# FPGA_Banks.net
KiCad netlist of a schematic drawn in Altium Designer
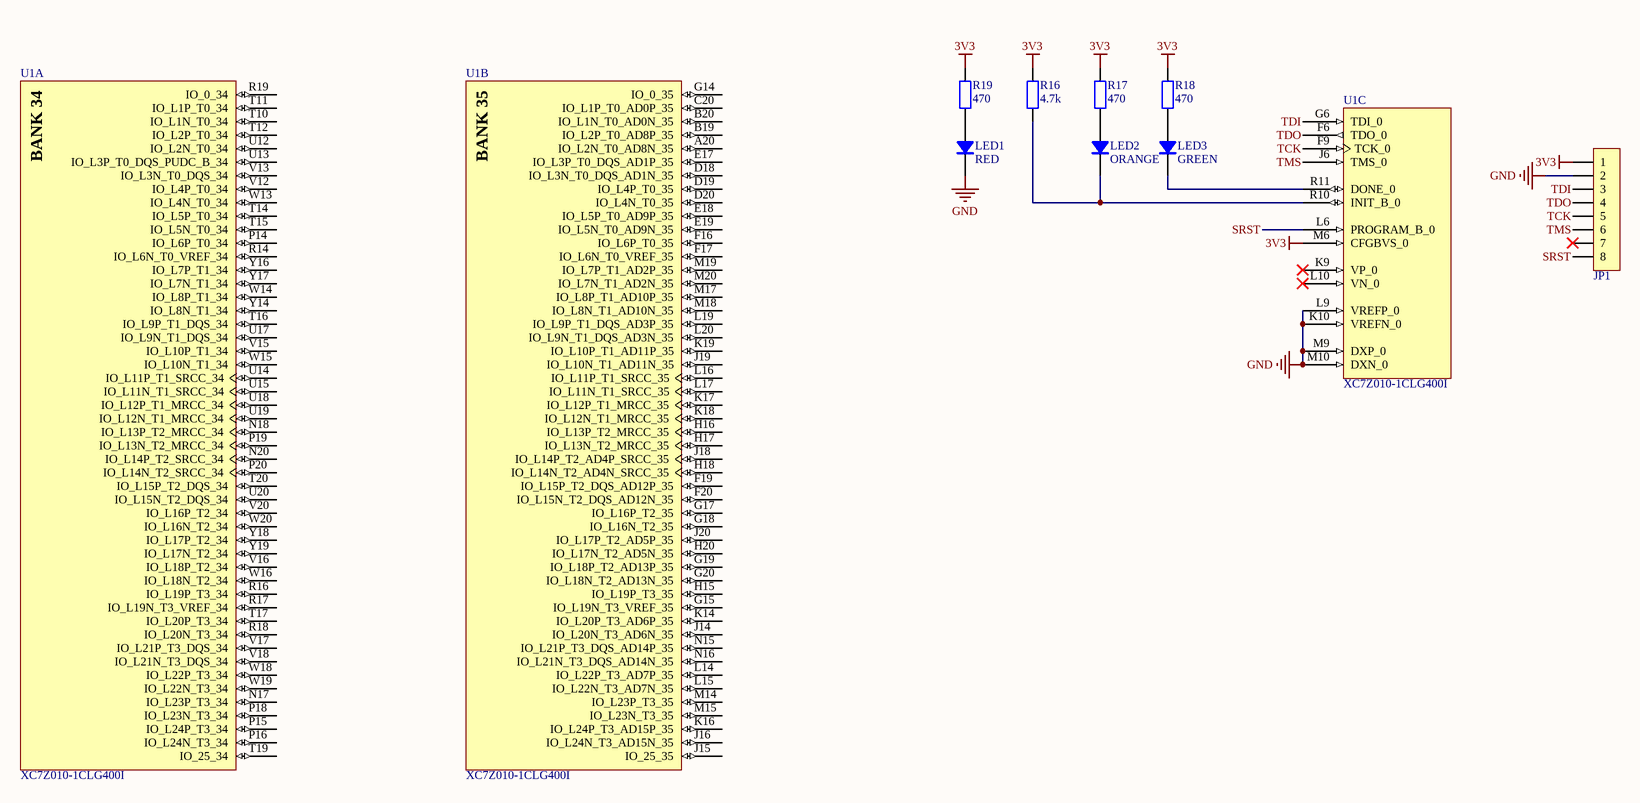
[diagram p0: FPGA_Banks.SchDoc]

(export (version "E")
  (design (tool "Eeschema 10.0.6"))
  (components
    (comp (ref "JP1")
      (value "HDR-1X8")
      (footprint "HDR2.54-LI-8P")
      (description "8P接插件")
      (fields (field (name "版权归属") "源创客"))
      (libsource (lib "Pin2.54") (part "Header 8"))
    )
    (comp (ref "LED1") (value "RED") (footprint "LED 0603R") (libsource (lib "Passive") (part "D")))
    (comp (ref "LED2") (value "ORANGE") (footprint "LED 0603Y") (libsource (lib "Passive") (part "D")))
    (comp (ref "LED3") (value "GREEN") (footprint "LED 0603G") (libsource (lib "Passive") (part "D")))
    (comp (ref "R16") (value "4.7k") (footprint "R0402") (libsource (lib "Passive") (part "R")))
    (comp (ref "R17") (value "470") (footprint "R0402") (libsource (lib "Passive") (part "R")))
    (comp (ref "R18") (value "470") (footprint "R0402") (libsource (lib "Passive") (part "R")))
    (comp (ref "R19") (value "470") (footprint "R0402") (libsource (lib "Passive") (part "R")))
    (comp (ref "U1")
      (value "XC7Z010-1CLG400I")
      (footprint "CLG400")
      (fields (field (name "GENERIC PART NUMBER") "XC7Z010"))
      (libsource (lib "Altium Content Vault") (part "XNLX-XC7Z010-CLG400"))
    )
  )
  (nets
    (net (code "1") (name "/SRST") (class "Default")
      (node (ref "JP1") (pin "8") (pinfunction "8_8") (pintype "passive"))
      (node (ref "U1") (pin "L6") (pinfunction "PROGRAM_B_0_L6") (pintype "input"))
    )
    (net (code "2") (name "/TCK") (class "Default")
      (node (ref "JP1") (pin "5") (pinfunction "5_5") (pintype "passive"))
      (node (ref "U1") (pin "F9") (pinfunction "TCK_0_F9") (pintype "input"))
    )
    (net (code "3") (name "/TDI") (class "Default")
      (node (ref "JP1") (pin "3") (pinfunction "3_3") (pintype "passive"))
      (node (ref "U1") (pin "G6") (pinfunction "TDI_0_G6") (pintype "input"))
    )
    (net (code "4") (name "/TDO") (class "Default")
      (node (ref "JP1") (pin "4") (pinfunction "4_4") (pintype "passive"))
      (node (ref "U1") (pin "F6") (pinfunction "TDO_0_F6") (pintype "output"))
    )
    (net (code "5") (name "/TMS") (class "Default")
      (node (ref "JP1") (pin "6") (pinfunction "6_6") (pintype "passive"))
      (node (ref "U1") (pin "J6") (pinfunction "TMS_0_J6") (pintype "input"))
    )
    (net (code "6") (name "3V3") (class "Default")
      (node (ref "JP1") (pin "1") (pinfunction "1_1") (pintype "passive"))
      (node (ref "R16") (pin "1") (pinfunction "1_1") (pintype "passive"))
      (node (ref "R17") (pin "1") (pinfunction "1_1") (pintype "passive"))
      (node (ref "R18") (pin "1") (pinfunction "1_1") (pintype "passive"))
      (node (ref "R19") (pin "1") (pinfunction "1_1") (pintype "passive"))
      (node (ref "U1") (pin "M6") (pinfunction "CFGBVS_0_M6") (pintype "input"))
    )
    (net (code "7") (name "GND") (class "Default")
      (node (ref "JP1") (pin "2") (pinfunction "2_2") (pintype "passive"))
      (node (ref "LED1") (pin "2") (pinfunction "K_2") (pintype "passive"))
      (node (ref "U1") (pin "K10") (pinfunction "VREFN_0_K10") (pintype "input"))
      (node (ref "U1") (pin "L9") (pinfunction "VREFP_0_L9") (pintype "input"))
      (node (ref "U1") (pin "M10") (pinfunction "DXN_0_M10") (pintype "input"))
      (node (ref "U1") (pin "M9") (pinfunction "DXP_0_M9") (pintype "input"))
    )
    (net (code "8") (name "Net-(LED1-A)") (class "Default")
      (node (ref "LED1") (pin "1") (pinfunction "A_1") (pintype "passive"))
      (node (ref "R19") (pin "2") (pinfunction "2_2") (pintype "passive"))
    )
    (net (code "9") (name "Net-(LED2-A)") (class "Default")
      (node (ref "LED2") (pin "1") (pinfunction "A_1") (pintype "passive"))
      (node (ref "R17") (pin "2") (pinfunction "2_2") (pintype "passive"))
    )
    (net (code "10") (name "Net-(LED2-K)") (class "Default")
      (node (ref "LED2") (pin "2") (pinfunction "K_2") (pintype "passive"))
      (node (ref "R16") (pin "2") (pinfunction "2_2") (pintype "passive"))
      (node (ref "U1") (pin "R10") (pinfunction "INIT_B_0_R10") (pintype "bidirectional"))
    )
    (net (code "11") (name "Net-(LED3-A)") (class "Default")
      (node (ref "LED3") (pin "1") (pinfunction "A_1") (pintype "passive"))
      (node (ref "R18") (pin "2") (pinfunction "2_2") (pintype "passive"))
    )
    (net (code "12") (name "Net-(LED3-K)") (class "Default")
      (node (ref "LED3") (pin "2") (pinfunction "K_2") (pintype "passive"))
      (node (ref "U1") (pin "R11") (pinfunction "DONE_0_R11") (pintype "bidirectional"))
    )
    (net (code "13") (name "unconnected-(JP1-Pad7)") (class "Default")
      (node (ref "JP1") (pin "7") (pinfunction "7_7") (pintype "passive+no_connect"))
    )
    (net (code "14") (name "unconnected-(U1A-IO_0_34-PadR19)") (class "Default")
      (node (ref "U1") (pin "R19") (pinfunction "IO_0_34_R19") (pintype "bidirectional"))
    )
    (net (code "15") (name "unconnected-(U1A-IO_25_34-PadT19)") (class "Default")
      (node (ref "U1") (pin "T19") (pinfunction "IO_25_34_T19") (pintype "bidirectional"))
    )
    (net (code "16") (name "unconnected-(U1A-IO_L1N_T0_34-PadT10)") (class "Default")
      (node (ref "U1") (pin "T10") (pinfunction "IO_L1N_T0_34_T10") (pintype "bidirectional"))
    )
    (net (code "17") (name "unconnected-(U1A-IO_L1P_T0_34-PadT11)") (class "Default")
      (node (ref "U1") (pin "T11") (pinfunction "IO_L1P_T0_34_T11") (pintype "bidirectional"))
    )
    (net (code "18") (name "unconnected-(U1A-IO_L2N_T0_34-PadU12)") (class "Default")
      (node (ref "U1") (pin "U12") (pinfunction "IO_L2N_T0_34_U12") (pintype "bidirectional"))
    )
    (net (code "19") (name "unconnected-(U1A-IO_L2P_T0_34-PadT12)") (class "Default")
      (node (ref "U1") (pin "T12") (pinfunction "IO_L2P_T0_34_T12") (pintype "bidirectional"))
    )
    (net (code "20") (name "unconnected-(U1A-IO_L3N_T0_DQS_34-PadV13)") (class "Default")
      (node (ref "U1") (pin "V13") (pinfunction "IO_L3N_T0_DQS_34_V13") (pintype "bidirectional"))
    )
    (net (code "21") (name "unconnected-(U1A-IO_L3P_T0_DQS_PUDC_B_34-PadU13)") (class "Default")
      (node (ref "U1") (pin "U13") (pinfunction "IO_L3P_T0_DQS_PUDC_B_34_U13") (pintype "bidirectional"))
    )
    (net (code "22") (name "unconnected-(U1A-IO_L4N_T0_34-PadW13)") (class "Default")
      (node (ref "U1") (pin "W13") (pinfunction "IO_L4N_T0_34_W13") (pintype "bidirectional"))
    )
    (net (code "23") (name "unconnected-(U1A-IO_L4P_T0_34-PadV12)") (class "Default")
      (node (ref "U1") (pin "V12") (pinfunction "IO_L4P_T0_34_V12") (pintype "bidirectional"))
    )
    (net (code "24") (name "unconnected-(U1A-IO_L5N_T0_34-PadT15)") (class "Default")
      (node (ref "U1") (pin "T15") (pinfunction "IO_L5N_T0_34_T15") (pintype "bidirectional"))
    )
    (net (code "25") (name "unconnected-(U1A-IO_L5P_T0_34-PadT14)") (class "Default")
      (node (ref "U1") (pin "T14") (pinfunction "IO_L5P_T0_34_T14") (pintype "bidirectional"))
    )
    (net (code "26") (name "unconnected-(U1A-IO_L6N_T0_VREF_34-PadR14)") (class "Default")
      (node (ref "U1") (pin "R14") (pinfunction "IO_L6N_T0_VREF_34_R14") (pintype "bidirectional"))
    )
    (net (code "27") (name "unconnected-(U1A-IO_L6P_T0_34-PadP14)") (class "Default")
      (node (ref "U1") (pin "P14") (pinfunction "IO_L6P_T0_34_P14") (pintype "bidirectional"))
    )
    (net (code "28") (name "unconnected-(U1A-IO_L7N_T1_34-PadY17)") (class "Default")
      (node (ref "U1") (pin "Y17") (pinfunction "IO_L7N_T1_34_Y17") (pintype "bidirectional"))
    )
    (net (code "29") (name "unconnected-(U1A-IO_L7P_T1_34-PadY16)") (class "Default")
      (node (ref "U1") (pin "Y16") (pinfunction "IO_L7P_T1_34_Y16") (pintype "bidirectional"))
    )
    (net (code "30") (name "unconnected-(U1A-IO_L8N_T1_34-PadY14)") (class "Default")
      (node (ref "U1") (pin "Y14") (pinfunction "IO_L8N_T1_34_Y14") (pintype "bidirectional"))
    )
    (net (code "31") (name "unconnected-(U1A-IO_L8P_T1_34-PadW14)") (class "Default")
      (node (ref "U1") (pin "W14") (pinfunction "IO_L8P_T1_34_W14") (pintype "bidirectional"))
    )
    (net (code "32") (name "unconnected-(U1A-IO_L9N_T1_DQS_34-PadU17)") (class "Default")
      (node (ref "U1") (pin "U17") (pinfunction "IO_L9N_T1_DQS_34_U17") (pintype "bidirectional"))
    )
    (net (code "33") (name "unconnected-(U1A-IO_L9P_T1_DQS_34-PadT16)") (class "Default")
      (node (ref "U1") (pin "T16") (pinfunction "IO_L9P_T1_DQS_34_T16") (pintype "bidirectional"))
    )
    (net (code "34") (name "unconnected-(U1A-IO_L10N_T1_34-PadW15)") (class "Default")
      (node (ref "U1") (pin "W15") (pinfunction "IO_L10N_T1_34_W15") (pintype "bidirectional"))
    )
    (net (code "35") (name "unconnected-(U1A-IO_L10P_T1_34-PadV15)") (class "Default")
      (node (ref "U1") (pin "V15") (pinfunction "IO_L10P_T1_34_V15") (pintype "bidirectional"))
    )
    (net (code "36") (name "unconnected-(U1A-IO_L11N_T1_SRCC_34-PadU15)") (class "Default")
      (node (ref "U1") (pin "U15") (pinfunction "IO_L11N_T1_SRCC_34_U15") (pintype "bidirectional"))
    )
    (net (code "37") (name "unconnected-(U1A-IO_L11P_T1_SRCC_34-PadU14)") (class "Default")
      (node (ref "U1") (pin "U14") (pinfunction "IO_L11P_T1_SRCC_34_U14") (pintype "bidirectional"))
    )
    (net (code "38") (name "unconnected-(U1A-IO_L12N_T1_MRCC_34-PadU19)") (class "Default")
      (node (ref "U1") (pin "U19") (pinfunction "IO_L12N_T1_MRCC_34_U19") (pintype "bidirectional"))
    )
    (net (code "39") (name "unconnected-(U1A-IO_L12P_T1_MRCC_34-PadU18)") (class "Default")
      (node (ref "U1") (pin "U18") (pinfunction "IO_L12P_T1_MRCC_34_U18") (pintype "bidirectional"))
    )
    (net (code "40") (name "unconnected-(U1A-IO_L13N_T2_MRCC_34-PadP19)") (class "Default")
      (node (ref "U1") (pin "P19") (pinfunction "IO_L13N_T2_MRCC_34_P19") (pintype "bidirectional"))
    )
    (net (code "41") (name "unconnected-(U1A-IO_L13P_T2_MRCC_34-PadN18)") (class "Default")
      (node (ref "U1") (pin "N18") (pinfunction "IO_L13P_T2_MRCC_34_N18") (pintype "bidirectional"))
    )
    (net (code "42") (name "unconnected-(U1A-IO_L14N_T2_SRCC_34-PadP20)") (class "Default")
      (node (ref "U1") (pin "P20") (pinfunction "IO_L14N_T2_SRCC_34_P20") (pintype "bidirectional"))
    )
    (net (code "43") (name "unconnected-(U1A-IO_L14P_T2_SRCC_34-PadN20)") (class "Default")
      (node (ref "U1") (pin "N20") (pinfunction "IO_L14P_T2_SRCC_34_N20") (pintype "bidirectional"))
    )
    (net (code "44") (name "unconnected-(U1A-IO_L15N_T2_DQS_34-PadU20)") (class "Default")
      (node (ref "U1") (pin "U20") (pinfunction "IO_L15N_T2_DQS_34_U20") (pintype "bidirectional"))
    )
    (net (code "45") (name "unconnected-(U1A-IO_L15P_T2_DQS_34-PadT20)") (class "Default")
      (node (ref "U1") (pin "T20") (pinfunction "IO_L15P_T2_DQS_34_T20") (pintype "bidirectional"))
    )
    (net (code "46") (name "unconnected-(U1A-IO_L16N_T2_34-PadW20)") (class "Default")
      (node (ref "U1") (pin "W20") (pinfunction "IO_L16N_T2_34_W20") (pintype "bidirectional"))
    )
    (net (code "47") (name "unconnected-(U1A-IO_L16P_T2_34-PadV20)") (class "Default")
      (node (ref "U1") (pin "V20") (pinfunction "IO_L16P_T2_34_V20") (pintype "bidirectional"))
    )
    (net (code "48") (name "unconnected-(U1A-IO_L17N_T2_34-PadY19)") (class "Default")
      (node (ref "U1") (pin "Y19") (pinfunction "IO_L17N_T2_34_Y19") (pintype "bidirectional"))
    )
    (net (code "49") (name "unconnected-(U1A-IO_L17P_T2_34-PadY18)") (class "Default")
      (node (ref "U1") (pin "Y18") (pinfunction "IO_L17P_T2_34_Y18") (pintype "bidirectional"))
    )
    (net (code "50") (name "unconnected-(U1A-IO_L18N_T2_34-PadW16)") (class "Default")
      (node (ref "U1") (pin "W16") (pinfunction "IO_L18N_T2_34_W16") (pintype "bidirectional"))
    )
    (net (code "51") (name "unconnected-(U1A-IO_L18P_T2_34-PadV16)") (class "Default")
      (node (ref "U1") (pin "V16") (pinfunction "IO_L18P_T2_34_V16") (pintype "bidirectional"))
    )
    (net (code "52") (name "unconnected-(U1A-IO_L19N_T3_VREF_34-PadR17)") (class "Default")
      (node (ref "U1") (pin "R17") (pinfunction "IO_L19N_T3_VREF_34_R17") (pintype "bidirectional"))
    )
    (net (code "53") (name "unconnected-(U1A-IO_L19P_T3_34-PadR16)") (class "Default")
      (node (ref "U1") (pin "R16") (pinfunction "IO_L19P_T3_34_R16") (pintype "bidirectional"))
    )
    (net (code "54") (name "unconnected-(U1A-IO_L20N_T3_34-PadR18)") (class "Default")
      (node (ref "U1") (pin "R18") (pinfunction "IO_L20N_T3_34_R18") (pintype "bidirectional"))
    )
    (net (code "55") (name "unconnected-(U1A-IO_L20P_T3_34-PadT17)") (class "Default")
      (node (ref "U1") (pin "T17") (pinfunction "IO_L20P_T3_34_T17") (pintype "bidirectional"))
    )
    (net (code "56") (name "unconnected-(U1A-IO_L21N_T3_DQS_34-PadV18)") (class "Default")
      (node (ref "U1") (pin "V18") (pinfunction "IO_L21N_T3_DQS_34_V18") (pintype "bidirectional"))
    )
    (net (code "57") (name "unconnected-(U1A-IO_L21P_T3_DQS_34-PadV17)") (class "Default")
      (node (ref "U1") (pin "V17") (pinfunction "IO_L21P_T3_DQS_34_V17") (pintype "bidirectional"))
    )
    (net (code "58") (name "unconnected-(U1A-IO_L22N_T3_34-PadW19)") (class "Default")
      (node (ref "U1") (pin "W19") (pinfunction "IO_L22N_T3_34_W19") (pintype "bidirectional"))
    )
    (net (code "59") (name "unconnected-(U1A-IO_L22P_T3_34-PadW18)") (class "Default")
      (node (ref "U1") (pin "W18") (pinfunction "IO_L22P_T3_34_W18") (pintype "bidirectional"))
    )
    (net (code "60") (name "unconnected-(U1A-IO_L23N_T3_34-PadP18)") (class "Default")
      (node (ref "U1") (pin "P18") (pinfunction "IO_L23N_T3_34_P18") (pintype "bidirectional"))
    )
    (net (code "61") (name "unconnected-(U1A-IO_L23P_T3_34-PadN17)") (class "Default")
      (node (ref "U1") (pin "N17") (pinfunction "IO_L23P_T3_34_N17") (pintype "bidirectional"))
    )
    (net (code "62") (name "unconnected-(U1A-IO_L24N_T3_34-PadP16)") (class "Default")
      (node (ref "U1") (pin "P16") (pinfunction "IO_L24N_T3_34_P16") (pintype "bidirectional"))
    )
    (net (code "63") (name "unconnected-(U1A-IO_L24P_T3_34-PadP15)") (class "Default")
      (node (ref "U1") (pin "P15") (pinfunction "IO_L24P_T3_34_P15") (pintype "bidirectional"))
    )
    (net (code "64") (name "unconnected-(U1B-IO_0_35-PadG14)") (class "Default")
      (node (ref "U1") (pin "G14") (pinfunction "IO_0_35_G14") (pintype "bidirectional"))
    )
    (net (code "65") (name "unconnected-(U1B-IO_25_35-PadJ15)") (class "Default")
      (node (ref "U1") (pin "J15") (pinfunction "IO_25_35_J15") (pintype "bidirectional"))
    )
    (net (code "66") (name "unconnected-(U1B-IO_L1N_T0_AD0N_35-PadB20)") (class "Default")
      (node (ref "U1") (pin "B20") (pinfunction "IO_L1N_T0_AD0N_35_B20") (pintype "bidirectional"))
    )
    (net (code "67") (name "unconnected-(U1B-IO_L1P_T0_AD0P_35-PadC20)") (class "Default")
      (node (ref "U1") (pin "C20") (pinfunction "IO_L1P_T0_AD0P_35_C20") (pintype "bidirectional"))
    )
    (net (code "68") (name "unconnected-(U1B-IO_L2N_T0_AD8N_35-PadA20)") (class "Default")
      (node (ref "U1") (pin "A20") (pinfunction "IO_L2N_T0_AD8N_35_A20") (pintype "bidirectional"))
    )
    (net (code "69") (name "unconnected-(U1B-IO_L2P_T0_AD8P_35-PadB19)") (class "Default")
      (node (ref "U1") (pin "B19") (pinfunction "IO_L2P_T0_AD8P_35_B19") (pintype "bidirectional"))
    )
    (net (code "70") (name "unconnected-(U1B-IO_L3N_T0_DQS_AD1N_35-PadD18)") (class "Default")
      (node (ref "U1") (pin "D18") (pinfunction "IO_L3N_T0_DQS_AD1N_35_D18") (pintype "bidirectional"))
    )
    (net (code "71") (name "unconnected-(U1B-IO_L3P_T0_DQS_AD1P_35-PadE17)") (class "Default")
      (node (ref "U1") (pin "E17") (pinfunction "IO_L3P_T0_DQS_AD1P_35_E17") (pintype "bidirectional"))
    )
    (net (code "72") (name "unconnected-(U1B-IO_L4N_T0_35-PadD20)") (class "Default")
      (node (ref "U1") (pin "D20") (pinfunction "IO_L4N_T0_35_D20") (pintype "bidirectional"))
    )
    (net (code "73") (name "unconnected-(U1B-IO_L4P_T0_35-PadD19)") (class "Default")
      (node (ref "U1") (pin "D19") (pinfunction "IO_L4P_T0_35_D19") (pintype "bidirectional"))
    )
    (net (code "74") (name "unconnected-(U1B-IO_L5N_T0_AD9N_35-PadE19)") (class "Default")
      (node (ref "U1") (pin "E19") (pinfunction "IO_L5N_T0_AD9N_35_E19") (pintype "bidirectional"))
    )
    (net (code "75") (name "unconnected-(U1B-IO_L5P_T0_AD9P_35-PadE18)") (class "Default")
      (node (ref "U1") (pin "E18") (pinfunction "IO_L5P_T0_AD9P_35_E18") (pintype "bidirectional"))
    )
    (net (code "76") (name "unconnected-(U1B-IO_L6N_T0_VREF_35-PadF17)") (class "Default")
      (node (ref "U1") (pin "F17") (pinfunction "IO_L6N_T0_VREF_35_F17") (pintype "bidirectional"))
    )
    (net (code "77") (name "unconnected-(U1B-IO_L6P_T0_35-PadF16)") (class "Default")
      (node (ref "U1") (pin "F16") (pinfunction "IO_L6P_T0_35_F16") (pintype "bidirectional"))
    )
    (net (code "78") (name "unconnected-(U1B-IO_L7N_T1_AD2N_35-PadM20)") (class "Default")
      (node (ref "U1") (pin "M20") (pinfunction "IO_L7N_T1_AD2N_35_M20") (pintype "bidirectional"))
    )
    (net (code "79") (name "unconnected-(U1B-IO_L7P_T1_AD2P_35-PadM19)") (class "Default")
      (node (ref "U1") (pin "M19") (pinfunction "IO_L7P_T1_AD2P_35_M19") (pintype "bidirectional"))
    )
    (net (code "80") (name "unconnected-(U1B-IO_L8N_T1_AD10N_35-PadM18)") (class "Default")
      (node (ref "U1") (pin "M18") (pinfunction "IO_L8N_T1_AD10N_35_M18") (pintype "bidirectional"))
    )
    (net (code "81") (name "unconnected-(U1B-IO_L8P_T1_AD10P_35-PadM17)") (class "Default")
      (node (ref "U1") (pin "M17") (pinfunction "IO_L8P_T1_AD10P_35_M17") (pintype "bidirectional"))
    )
    (net (code "82") (name "unconnected-(U1B-IO_L9N_T1_DQS_AD3N_35-PadL20)") (class "Default")
      (node (ref "U1") (pin "L20") (pinfunction "IO_L9N_T1_DQS_AD3N_35_L20") (pintype "bidirectional"))
    )
    (net (code "83") (name "unconnected-(U1B-IO_L9P_T1_DQS_AD3P_35-PadL19)") (class "Default")
      (node (ref "U1") (pin "L19") (pinfunction "IO_L9P_T1_DQS_AD3P_35_L19") (pintype "bidirectional"))
    )
    (net (code "84") (name "unconnected-(U1B-IO_L10N_T1_AD11N_35-PadJ19)") (class "Default")
      (node (ref "U1") (pin "J19") (pinfunction "IO_L10N_T1_AD11N_35_J19") (pintype "bidirectional"))
    )
    (net (code "85") (name "unconnected-(U1B-IO_L10P_T1_AD11P_35-PadK19)") (class "Default")
      (node (ref "U1") (pin "K19") (pinfunction "IO_L10P_T1_AD11P_35_K19") (pintype "bidirectional"))
    )
    (net (code "86") (name "unconnected-(U1B-IO_L11N_T1_SRCC_35-PadL17)") (class "Default")
      (node (ref "U1") (pin "L17") (pinfunction "IO_L11N_T1_SRCC_35_L17") (pintype "bidirectional"))
    )
    (net (code "87") (name "unconnected-(U1B-IO_L11P_T1_SRCC_35-PadL16)") (class "Default")
      (node (ref "U1") (pin "L16") (pinfunction "IO_L11P_T1_SRCC_35_L16") (pintype "bidirectional"))
    )
    (net (code "88") (name "unconnected-(U1B-IO_L12N_T1_MRCC_35-PadK18)") (class "Default")
      (node (ref "U1") (pin "K18") (pinfunction "IO_L12N_T1_MRCC_35_K18") (pintype "bidirectional"))
    )
    (net (code "89") (name "unconnected-(U1B-IO_L12P_T1_MRCC_35-PadK17)") (class "Default")
      (node (ref "U1") (pin "K17") (pinfunction "IO_L12P_T1_MRCC_35_K17") (pintype "bidirectional"))
    )
    (net (code "90") (name "unconnected-(U1B-IO_L13N_T2_MRCC_35-PadH17)") (class "Default")
      (node (ref "U1") (pin "H17") (pinfunction "IO_L13N_T2_MRCC_35_H17") (pintype "bidirectional"))
    )
    (net (code "91") (name "unconnected-(U1B-IO_L13P_T2_MRCC_35-PadH16)") (class "Default")
      (node (ref "U1") (pin "H16") (pinfunction "IO_L13P_T2_MRCC_35_H16") (pintype "bidirectional"))
    )
    (net (code "92") (name "unconnected-(U1B-IO_L14N_T2_AD4N_SRCC_35-PadH18)") (class "Default")
      (node (ref "U1") (pin "H18") (pinfunction "IO_L14N_T2_AD4N_SRCC_35_H18") (pintype "bidirectional"))
    )
    (net (code "93") (name "unconnected-(U1B-IO_L14P_T2_AD4P_SRCC_35-PadJ18)") (class "Default")
      (node (ref "U1") (pin "J18") (pinfunction "IO_L14P_T2_AD4P_SRCC_35_J18") (pintype "bidirectional"))
    )
    (net (code "94") (name "unconnected-(U1B-IO_L15N_T2_DQS_AD12N_35-PadF20)") (class "Default")
      (node (ref "U1") (pin "F20") (pinfunction "IO_L15N_T2_DQS_AD12N_35_F20") (pintype "bidirectional"))
    )
    (net (code "95") (name "unconnected-(U1B-IO_L15P_T2_DQS_AD12P_35-PadF19)") (class "Default")
      (node (ref "U1") (pin "F19") (pinfunction "IO_L15P_T2_DQS_AD12P_35_F19") (pintype "bidirectional"))
    )
    (net (code "96") (name "unconnected-(U1B-IO_L16N_T2_35-PadG18)") (class "Default")
      (node (ref "U1") (pin "G18") (pinfunction "IO_L16N_T2_35_G18") (pintype "bidirectional"))
    )
    (net (code "97") (name "unconnected-(U1B-IO_L16P_T2_35-PadG17)") (class "Default")
      (node (ref "U1") (pin "G17") (pinfunction "IO_L16P_T2_35_G17") (pintype "bidirectional"))
    )
    (net (code "98") (name "unconnected-(U1B-IO_L17N_T2_AD5N_35-PadH20)") (class "Default")
      (node (ref "U1") (pin "H20") (pinfunction "IO_L17N_T2_AD5N_35_H20") (pintype "bidirectional"))
    )
    (net (code "99") (name "unconnected-(U1B-IO_L17P_T2_AD5P_35-PadJ20)") (class "Default")
      (node (ref "U1") (pin "J20") (pinfunction "IO_L17P_T2_AD5P_35_J20") (pintype "bidirectional"))
    )
    (net (code "100") (name "unconnected-(U1B-IO_L18N_T2_AD13N_35-PadG20)") (class "Default")
      (node (ref "U1") (pin "G20") (pinfunction "IO_L18N_T2_AD13N_35_G20") (pintype "bidirectional"))
    )
    (net (code "101") (name "unconnected-(U1B-IO_L18P_T2_AD13P_35-PadG19)") (class "Default")
      (node (ref "U1") (pin "G19") (pinfunction "IO_L18P_T2_AD13P_35_G19") (pintype "bidirectional"))
    )
    (net (code "102") (name "unconnected-(U1B-IO_L19N_T3_VREF_35-PadG15)") (class "Default")
      (node (ref "U1") (pin "G15") (pinfunction "IO_L19N_T3_VREF_35_G15") (pintype "bidirectional"))
    )
    (net (code "103") (name "unconnected-(U1B-IO_L19P_T3_35-PadH15)") (class "Default")
      (node (ref "U1") (pin "H15") (pinfunction "IO_L19P_T3_35_H15") (pintype "bidirectional"))
    )
    (net (code "104") (name "unconnected-(U1B-IO_L20N_T3_AD6N_35-PadJ14)") (class "Default")
      (node (ref "U1") (pin "J14") (pinfunction "IO_L20N_T3_AD6N_35_J14") (pintype "bidirectional"))
    )
    (net (code "105") (name "unconnected-(U1B-IO_L20P_T3_AD6P_35-PadK14)") (class "Default")
      (node (ref "U1") (pin "K14") (pinfunction "IO_L20P_T3_AD6P_35_K14") (pintype "bidirectional"))
    )
    (net (code "106") (name "unconnected-(U1B-IO_L21N_T3_DQS_AD14N_35-PadN16)") (class "Default")
      (node (ref "U1") (pin "N16") (pinfunction "IO_L21N_T3_DQS_AD14N_35_N16") (pintype "bidirectional"))
    )
    (net (code "107") (name "unconnected-(U1B-IO_L21P_T3_DQS_AD14P_35-PadN15)") (class "Default")
      (node (ref "U1") (pin "N15") (pinfunction "IO_L21P_T3_DQS_AD14P_35_N15") (pintype "bidirectional"))
    )
    (net (code "108") (name "unconnected-(U1B-IO_L22N_T3_AD7N_35-PadL15)") (class "Default")
      (node (ref "U1") (pin "L15") (pinfunction "IO_L22N_T3_AD7N_35_L15") (pintype "bidirectional"))
    )
    (net (code "109") (name "unconnected-(U1B-IO_L22P_T3_AD7P_35-PadL14)") (class "Default")
      (node (ref "U1") (pin "L14") (pinfunction "IO_L22P_T3_AD7P_35_L14") (pintype "bidirectional"))
    )
    (net (code "110") (name "unconnected-(U1B-IO_L23N_T3_35-PadM15)") (class "Default")
      (node (ref "U1") (pin "M15") (pinfunction "IO_L23N_T3_35_M15") (pintype "bidirectional"))
    )
    (net (code "111") (name "unconnected-(U1B-IO_L23P_T3_35-PadM14)") (class "Default")
      (node (ref "U1") (pin "M14") (pinfunction "IO_L23P_T3_35_M14") (pintype "bidirectional"))
    )
    (net (code "112") (name "unconnected-(U1B-IO_L24N_T3_AD15N_35-PadJ16)") (class "Default")
      (node (ref "U1") (pin "J16") (pinfunction "IO_L24N_T3_AD15N_35_J16") (pintype "bidirectional"))
    )
    (net (code "113") (name "unconnected-(U1B-IO_L24P_T3_AD15P_35-PadK16)") (class "Default")
      (node (ref "U1") (pin "K16") (pinfunction "IO_L24P_T3_AD15P_35_K16") (pintype "bidirectional"))
    )
    (net (code "114") (name "unconnected-(U1C-VN_0-PadL10)") (class "Default")
      (node (ref "U1") (pin "L10") (pinfunction "VN_0_L10") (pintype "input+no_connect"))
    )
    (net (code "115") (name "unconnected-(U1C-VP_0-PadK9)") (class "Default")
      (node (ref "U1") (pin "K9") (pinfunction "VP_0_K9") (pintype "input+no_connect"))
    )
  )
)
